# wing.net
KiCad netlist of a schematic drawn in Altium Designer
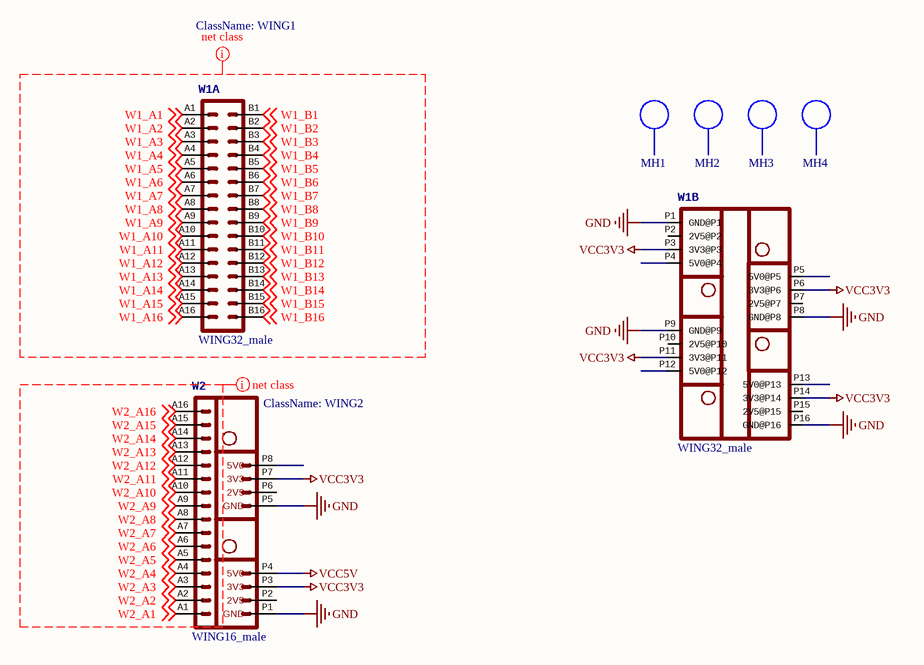
[diagram p0: wing.SchDoc]

(export (version "E")
  (design (tool "Eeschema 10.0.6"))
  (components
    (comp (ref "MH1")
      (value "MOUNTING HOLE")
      (footprint "MOUNTING_HOLE")
      (libsource (lib "Papilio") (part "MOUNTING_HOLE"))
    )
    (comp (ref "MH2")
      (value "MOUNTING HOLE")
      (footprint "MOUNTING_HOLE")
      (libsource (lib "Papilio") (part "MOUNTING_HOLE"))
    )
    (comp (ref "MH3")
      (value "MOUNTING HOLE")
      (footprint "MOUNTING_HOLE")
      (libsource (lib "Papilio") (part "MOUNTING_HOLE"))
    )
    (comp (ref "MH4")
      (value "MOUNTING HOLE")
      (footprint "MOUNTING_HOLE")
      (libsource (lib "Papilio") (part "MOUNTING_HOLE"))
    )
    (comp (ref "W1")
      (value "WING32_male")
      (footprint "WING32_HOLES - MALE")
      (libsource (lib "Papilio") (part "WING32_male"))
    )
    (comp (ref "W2")
      (value "WING16_male")
      (footprint "WINGSIDE_16BIT - male")
      (description "Papilio Wing16")
      (libsource (lib "Papilio") (part "WING16_male"))
    )
  )
  (nets
    (net (code "1") (name "GND") (class "Default")
      (node (ref "W1") (pin "P1") (pinfunction "GND@P1_P1") (pintype "power_in"))
      (node (ref "W1") (pin "P16") (pinfunction "GND@P16_P16") (pintype "power_in"))
      (node (ref "W1") (pin "P8") (pinfunction "GND@P8_P8") (pintype "power_in"))
      (node (ref "W1") (pin "P9") (pinfunction "GND@P9_P9") (pintype "power_in"))
      (node (ref "W2") (pin "P1") (pinfunction "GND_P1") (pintype "passive"))
      (node (ref "W2") (pin "P5") (pinfunction "GND_P5") (pintype "passive"))
    )
    (net (code "2") (name "VCC3V3") (class "Default")
      (node (ref "W1") (pin "P11") (pinfunction "3V3@P11_P11") (pintype "passive"))
      (node (ref "W1") (pin "P14") (pinfunction "3V3@P14_P14") (pintype "passive"))
      (node (ref "W1") (pin "P3") (pinfunction "3V3@P3_P3") (pintype "passive"))
      (node (ref "W1") (pin "P6") (pinfunction "3V3@P6_P6") (pintype "passive"))
      (node (ref "W2") (pin "P3") (pinfunction "3V3_P3") (pintype "passive"))
      (node (ref "W2") (pin "P7") (pinfunction "3V3_P7") (pintype "passive"))
    )
    (net (code "3") (name "VCC5V") (class "Default")
      (node (ref "W2") (pin "P4") (pinfunction "5V_P4") (pintype "passive"))
    )
    (net (code "4") (name "W1_A1") (class "Default")
      (node (ref "W1") (pin "A1") (pinfunction "A1_A1") (pintype "passive"))
    )
    (net (code "5") (name "W1_A2") (class "Default")
      (node (ref "W1") (pin "A2") (pinfunction "A2_A2") (pintype "passive"))
    )
    (net (code "6") (name "W1_A3") (class "Default")
      (node (ref "W1") (pin "A3") (pinfunction "A3_A3") (pintype "passive"))
    )
    (net (code "7") (name "W1_A4") (class "Default")
      (node (ref "W1") (pin "A4") (pinfunction "A4_A4") (pintype "passive"))
    )
    (net (code "8") (name "W1_A5") (class "Default")
      (node (ref "W1") (pin "A5") (pinfunction "A5_A5") (pintype "passive"))
    )
    (net (code "9") (name "W1_A6") (class "Default")
      (node (ref "W1") (pin "A6") (pinfunction "A6_A6") (pintype "passive"))
    )
    (net (code "10") (name "W1_A7") (class "Default")
      (node (ref "W1") (pin "A7") (pinfunction "A7_A7") (pintype "passive"))
    )
    (net (code "11") (name "W1_A8") (class "Default")
      (node (ref "W1") (pin "A8") (pinfunction "A8_A8") (pintype "passive"))
    )
    (net (code "12") (name "W1_A9") (class "Default")
      (node (ref "W1") (pin "A9") (pinfunction "A9_A9") (pintype "passive"))
    )
    (net (code "13") (name "W1_A10") (class "Default")
      (node (ref "W1") (pin "A10") (pinfunction "A10_A10") (pintype "passive"))
    )
    (net (code "14") (name "W1_A11") (class "Default")
      (node (ref "W1") (pin "A11") (pinfunction "A11_A11") (pintype "passive"))
    )
    (net (code "15") (name "W1_A12") (class "Default")
      (node (ref "W1") (pin "A12") (pinfunction "A12_A12") (pintype "passive"))
    )
    (net (code "16") (name "W1_A13") (class "Default")
      (node (ref "W1") (pin "A13") (pinfunction "A13_A13") (pintype "passive"))
    )
    (net (code "17") (name "W1_A14") (class "Default")
      (node (ref "W1") (pin "A14") (pinfunction "A14_A14") (pintype "passive"))
    )
    (net (code "18") (name "W1_A15") (class "Default")
      (node (ref "W1") (pin "A15") (pinfunction "A15_A15") (pintype "passive"))
    )
    (net (code "19") (name "W1_A16") (class "Default")
      (node (ref "W1") (pin "A16") (pinfunction "A16_A16") (pintype "passive"))
    )
    (net (code "20") (name "W1_B1") (class "Default")
      (node (ref "W1") (pin "B1") (pinfunction "B1_B1") (pintype "passive"))
    )
    (net (code "21") (name "W1_B2") (class "Default")
      (node (ref "W1") (pin "B2") (pinfunction "B2_B2") (pintype "passive"))
    )
    (net (code "22") (name "W1_B3") (class "Default")
      (node (ref "W1") (pin "B3") (pinfunction "B3_B3") (pintype "passive"))
    )
    (net (code "23") (name "W1_B4") (class "Default")
      (node (ref "W1") (pin "B4") (pinfunction "B4_B4") (pintype "passive"))
    )
    (net (code "24") (name "W1_B5") (class "Default")
      (node (ref "W1") (pin "B5") (pinfunction "B5_B5") (pintype "passive"))
    )
    (net (code "25") (name "W1_B6") (class "Default")
      (node (ref "W1") (pin "B6") (pinfunction "B6_B6") (pintype "passive"))
    )
    (net (code "26") (name "W1_B7") (class "Default")
      (node (ref "W1") (pin "B7") (pinfunction "B7_B7") (pintype "passive"))
    )
    (net (code "27") (name "W1_B8") (class "Default")
      (node (ref "W1") (pin "B8") (pinfunction "B8_B8") (pintype "passive"))
    )
    (net (code "28") (name "W1_B9") (class "Default")
      (node (ref "W1") (pin "B9") (pinfunction "B9_B9") (pintype "passive"))
    )
    (net (code "29") (name "W1_B10") (class "Default")
      (node (ref "W1") (pin "B10") (pinfunction "B10_B10") (pintype "passive"))
    )
    (net (code "30") (name "W1_B11") (class "Default")
      (node (ref "W1") (pin "B11") (pinfunction "B11_B11") (pintype "passive"))
    )
    (net (code "31") (name "W1_B12") (class "Default")
      (node (ref "W1") (pin "B12") (pinfunction "B12_B12") (pintype "passive"))
    )
    (net (code "32") (name "W1_B13") (class "Default")
      (node (ref "W1") (pin "B13") (pinfunction "B13_B13") (pintype "passive"))
    )
    (net (code "33") (name "W1_B14") (class "Default")
      (node (ref "W1") (pin "B14") (pinfunction "B14_B14") (pintype "passive"))
    )
    (net (code "34") (name "W1_B15") (class "Default")
      (node (ref "W1") (pin "B15") (pinfunction "B15_B15") (pintype "passive"))
    )
    (net (code "35") (name "W1_B16") (class "Default")
      (node (ref "W1") (pin "B16") (pinfunction "B16_B16") (pintype "passive"))
    )
    (net (code "36") (name "W2_A1") (class "Default")
      (node (ref "W2") (pin "A1") (pinfunction "A1_A1") (pintype "passive"))
    )
    (net (code "37") (name "W2_A2") (class "Default")
      (node (ref "W2") (pin "A2") (pinfunction "A2_A2") (pintype "passive"))
    )
    (net (code "38") (name "W2_A3") (class "Default")
      (node (ref "W2") (pin "A3") (pinfunction "A3_A3") (pintype "passive"))
    )
    (net (code "39") (name "W2_A4") (class "Default")
      (node (ref "W2") (pin "A4") (pinfunction "A4_A4") (pintype "passive"))
    )
    (net (code "40") (name "W2_A5") (class "Default")
      (node (ref "W2") (pin "A5") (pinfunction "A5_A5") (pintype "passive"))
    )
    (net (code "41") (name "W2_A6") (class "Default")
      (node (ref "W2") (pin "A6") (pinfunction "A6_A6") (pintype "passive"))
    )
    (net (code "42") (name "W2_A7") (class "Default")
      (node (ref "W2") (pin "A7") (pinfunction "A7_A7") (pintype "passive"))
    )
    (net (code "43") (name "W2_A8") (class "Default")
      (node (ref "W2") (pin "A8") (pinfunction "A8_A8") (pintype "passive"))
    )
    (net (code "44") (name "W2_A9") (class "Default")
      (node (ref "W2") (pin "A9") (pinfunction "A9_A9") (pintype "passive"))
    )
    (net (code "45") (name "W2_A10") (class "Default")
      (node (ref "W2") (pin "A10") (pinfunction "A10_A10") (pintype "passive"))
    )
    (net (code "46") (name "W2_A11") (class "Default")
      (node (ref "W2") (pin "A11") (pinfunction "A11_A11") (pintype "passive"))
    )
    (net (code "47") (name "W2_A12") (class "Default")
      (node (ref "W2") (pin "A12") (pinfunction "A12_A12") (pintype "passive"))
    )
    (net (code "48") (name "W2_A13") (class "Default")
      (node (ref "W2") (pin "A13") (pinfunction "A13_A13") (pintype "passive"))
    )
    (net (code "49") (name "W2_A14") (class "Default")
      (node (ref "W2") (pin "A14") (pinfunction "A14_A14") (pintype "passive"))
    )
    (net (code "50") (name "W2_A15") (class "Default")
      (node (ref "W2") (pin "A15") (pinfunction "A15_A15") (pintype "passive"))
    )
    (net (code "51") (name "W2_A16") (class "Default")
      (node (ref "W2") (pin "A16") (pinfunction "A16_A16") (pintype "passive"))
    )
    (net (code "52") (name "unconnected-(MH1-Pad1)") (class "Default")
      (node (ref "MH1") (pin "1") (pinfunction "1_1") (pintype "passive"))
    )
    (net (code "53") (name "unconnected-(MH2-Pad1)") (class "Default")
      (node (ref "MH2") (pin "1") (pinfunction "1_1") (pintype "passive"))
    )
    (net (code "54") (name "unconnected-(MH3-Pad1)") (class "Default")
      (node (ref "MH3") (pin "1") (pinfunction "1_1") (pintype "passive"))
    )
    (net (code "55") (name "unconnected-(MH4-Pad1)") (class "Default")
      (node (ref "MH4") (pin "1") (pinfunction "1_1") (pintype "passive"))
    )
    (net (code "56") (name "unconnected-(W1B-2V5@P2-PadP2)") (class "Default")
      (node (ref "W1") (pin "P2") (pinfunction "2V5@P2_P2") (pintype "passive"))
    )
    (net (code "57") (name "unconnected-(W1B-2V5@P7-PadP7)") (class "Default")
      (node (ref "W1") (pin "P7") (pinfunction "2V5@P7_P7") (pintype "passive"))
    )
    (net (code "58") (name "unconnected-(W1B-2V5@P10-PadP10)") (class "Default")
      (node (ref "W1") (pin "P10") (pinfunction "2V5@P10_P10") (pintype "passive"))
    )
    (net (code "59") (name "unconnected-(W1B-2V5@P15-PadP15)") (class "Default")
      (node (ref "W1") (pin "P15") (pinfunction "2V5@P15_P15") (pintype "passive"))
    )
    (net (code "60") (name "unconnected-(W1B-5V0@P4-PadP4)") (class "Default")
      (node (ref "W1") (pin "P4") (pinfunction "5V0@P4_P4") (pintype "passive"))
    )
    (net (code "61") (name "unconnected-(W1B-5V0@P5-PadP5)") (class "Default")
      (node (ref "W1") (pin "P5") (pinfunction "5V0@P5_P5") (pintype "passive"))
    )
    (net (code "62") (name "unconnected-(W1B-5V0@P12-PadP12)") (class "Default")
      (node (ref "W1") (pin "P12") (pinfunction "5V0@P12_P12") (pintype "passive"))
    )
    (net (code "63") (name "unconnected-(W1B-5V0@P13-PadP13)") (class "Default")
      (node (ref "W1") (pin "P13") (pinfunction "5V0@P13_P13") (pintype "passive"))
    )
    (net (code "64") (name "unconnected-(W2-2V2-PadP2)") (class "Default")
      (node (ref "W2") (pin "P2") (pinfunction "2V2_P2") (pintype "passive"))
    )
    (net (code "65") (name "unconnected-(W2-2V5-PadP6)") (class "Default")
      (node (ref "W2") (pin "P6") (pinfunction "2V5_P6") (pintype "passive"))
    )
    (net (code "66") (name "unconnected-(W2-5V-PadP8)") (class "Default")
      (node (ref "W2") (pin "P8") (pinfunction "5V_P8") (pintype "passive"))
    )
  )
)
